# igniterPCB.net
KiCad netlist of a schematic drawn in EAGLE
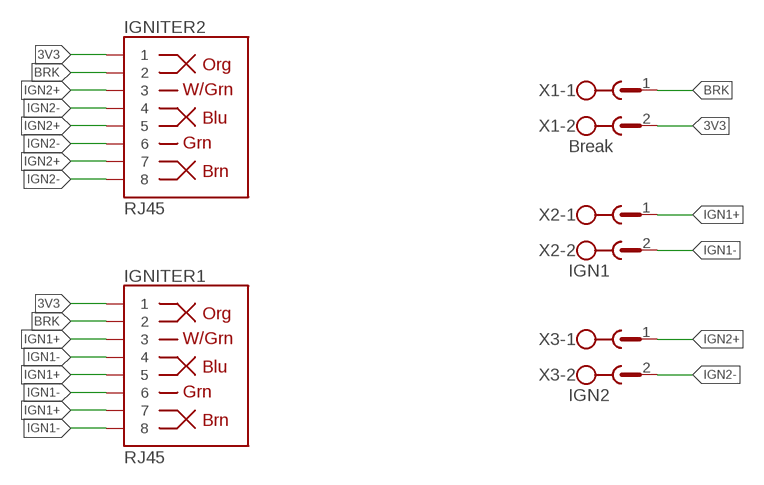
[diagram p0: schematic, sheet 1]

(export (version "E")
  (design (tool "Eeschema 10.0.6"))
  (components
    (comp (ref "IGNITER1")
      (value "RJ45")
      (footprint "eagle-import:RJ45-8")
      (libsource (lib "eagle-import") (part "RJ45-8PTH"))
    )
    (comp (ref "IGNITER2")
      (value "RJ45")
      (footprint "eagle-import:RJ45-8")
      (libsource (lib "eagle-import") (part "RJ45-8PTH"))
    )
    (comp (ref "X1")
      (value "Break")
      (footprint "eagle-import:MSTBA2")
      (fields (field (name "MF") "FARNELL") (field (name "MPN") "1757242"))
      (libsource (lib "eagle-import") (part "MSTBA2"))
    )
    (comp (ref "X2")
      (value "IGN1")
      (footprint "eagle-import:MSTBA2")
      (fields (field (name "MF") "FARNELL") (field (name "MPN") "1757242"))
      (libsource (lib "eagle-import") (part "MSTBA2"))
    )
    (comp (ref "X3")
      (value "IGN2")
      (footprint "eagle-import:MSTBA2")
      (fields (field (name "MF") "FARNELL") (field (name "MPN") "1757242"))
      (libsource (lib "eagle-import") (part "MSTBA2"))
    )
  )
  (nets
    (net (code "1") (name "3V3") (class "Default")
      (node (ref "IGNITER1") (pin "1") (pinfunction "1_1") (pintype "bidirectional"))
      (node (ref "IGNITER2") (pin "1") (pinfunction "1_1") (pintype "bidirectional"))
      (node (ref "X1") (pin "2") (pinfunction "1_2") (pintype "passive"))
    )
    (net (code "2") (name "BRK") (class "Default")
      (node (ref "IGNITER1") (pin "2") (pinfunction "2_2") (pintype "bidirectional"))
      (node (ref "IGNITER2") (pin "2") (pinfunction "2_2") (pintype "bidirectional"))
      (node (ref "X1") (pin "1") (pinfunction "1_1") (pintype "passive"))
    )
    (net (code "3") (name "IGN1+") (class "Default")
      (node (ref "IGNITER1") (pin "3") (pinfunction "3_3") (pintype "bidirectional"))
      (node (ref "IGNITER1") (pin "5") (pinfunction "5_5") (pintype "bidirectional"))
      (node (ref "IGNITER1") (pin "7") (pinfunction "7_7") (pintype "bidirectional"))
      (node (ref "X2") (pin "1") (pinfunction "1_1") (pintype "passive"))
    )
    (net (code "4") (name "IGN1-") (class "Default")
      (node (ref "IGNITER1") (pin "4") (pinfunction "4_4") (pintype "bidirectional"))
      (node (ref "IGNITER1") (pin "6") (pinfunction "6_6") (pintype "bidirectional"))
      (node (ref "IGNITER1") (pin "8") (pinfunction "8_8") (pintype "bidirectional"))
      (node (ref "X2") (pin "2") (pinfunction "1_2") (pintype "passive"))
    )
    (net (code "5") (name "IGN2+") (class "Default")
      (node (ref "IGNITER2") (pin "3") (pinfunction "3_3") (pintype "bidirectional"))
      (node (ref "IGNITER2") (pin "5") (pinfunction "5_5") (pintype "bidirectional"))
      (node (ref "IGNITER2") (pin "7") (pinfunction "7_7") (pintype "bidirectional"))
      (node (ref "X3") (pin "1") (pinfunction "1_1") (pintype "passive"))
    )
    (net (code "6") (name "IGN2-") (class "Default")
      (node (ref "IGNITER2") (pin "4") (pinfunction "4_4") (pintype "bidirectional"))
      (node (ref "IGNITER2") (pin "6") (pinfunction "6_6") (pintype "bidirectional"))
      (node (ref "IGNITER2") (pin "8") (pinfunction "8_8") (pintype "bidirectional"))
      (node (ref "X3") (pin "2") (pinfunction "1_2") (pintype "passive"))
    )
  )
)
